# 06-uSD_Buttons_and_Buzzer.net
KiCad netlist of a schematic drawn in Altium Designer
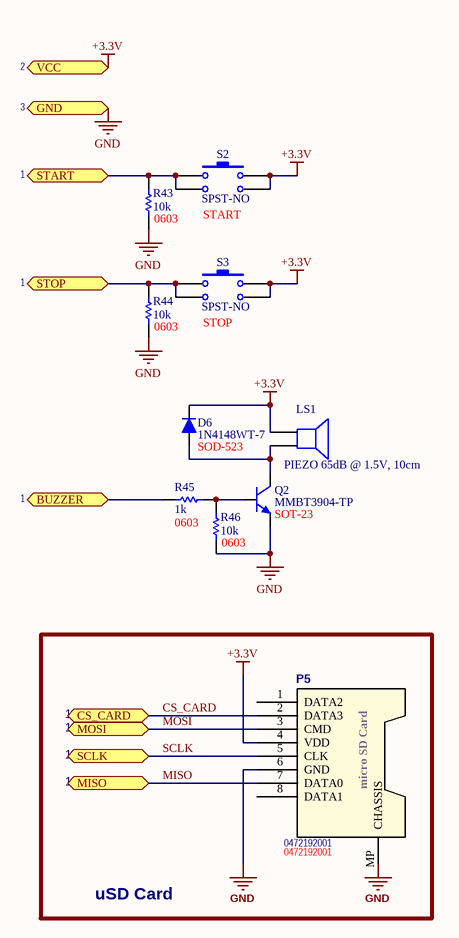
[diagram p0: 06-uSD, Buttons and Buzzer.SchDoc]

(export (version "E")
  (design (tool "Eeschema 10.0.6"))
  (components
    (comp (ref "D6")
      (value "1N4148WT-7")
      (footprint "SOD523")
      (description "Diode")
      (fields (field (name "PACKAGEREFERENCE") "SOD-523"))
      (libsource (lib "schematic_library") (part "DIODE"))
    )
    (comp (ref "LS1")
      (value "PIEZO 65dB @ 1.5V, 10cm")
      (footprint "PIEZO_XDCR_PKMCS0909E4000-R1")
      (description "Loudspeaker")
      (fields (field (name "MANUFACTURER PART NUMBER") "PKMCS0909E4000-R1"))
      (libsource (lib "Miscellaneous Devices") (part "Speaker"))
    )
    (comp (ref "P5")
      (value "0472192001")
      (footprint "MICROSD_MOLEX_0472192001")
      (description "Micro SD Card Slot 8-pin Push-In Push-Out")
      (fields (field (name "PACKAGEREFERENCE") "0472192001"))
      (libsource (lib "schematic_library") (part "microSD-114-00841-68"))
    )
    (comp (ref "Q2")
      (value "MMBT3904-TP")
      (footprint "SOT23-3")
      (description "TRANS NPN 40V 0.2A SOT-23")
      (fields (field (name "PACKAGEREFERENCE") "SOT-23"))
      (libsource (lib "schematic_library") (part "MMBT3904"))
    )
    (comp (ref "R43")
      (value "10k")
      (footprint "R0603")
      (description "Resistor")
      (fields
        (field (name "MANUFACTURER PART NUMBER") "RMCF0603FT10K0")
        (field (name "PACKAGEREFERENCE") "0603")
      )
      (libsource (lib "Miscellaneous Devices") (part "Res1"))
    )
    (comp (ref "R44")
      (value "10k")
      (footprint "R0603")
      (description "Resistor")
      (fields
        (field (name "MANUFACTURER PART NUMBER") "RMCF0603FT10K0")
        (field (name "PACKAGEREFERENCE") "0603")
      )
      (libsource (lib "Miscellaneous Devices") (part "Res1"))
    )
    (comp (ref "R45")
      (value "1k")
      (footprint "R0603")
      (description "Resistor")
      (fields
        (field (name "MANUFACTURER PART NUMBER") "RMCF0603FG1K00")
        (field (name "PACKAGEREFERENCE") "0603")
      )
      (libsource (lib "Miscellaneous Devices") (part "Res1"))
    )
    (comp (ref "R46")
      (value "10k")
      (footprint "R0603")
      (description "Resistor")
      (fields
        (field (name "MANUFACTURER PART NUMBER") "RMCF0603FT10K0")
        (field (name "PACKAGEREFERENCE") "0603")
      )
      (libsource (lib "Miscellaneous Devices") (part "Res1"))
    )
    (comp (ref "S2")
      (value "SPST-NO")
      (footprint "BUTTON_D6R90_GREEN")
      (description "Switch")
      (fields (field (name "MANUFACTURER PART NUMBER") "D6R50 F1 LFS") (field (name "FUNCTION") "START"))
      (libsource (lib "Library_Scott") (part "SW-PB"))
    )
    (comp (ref "S3")
      (value "SPST-NO")
      (footprint "BUTTON_D6R90_RED")
      (description "Switch")
      (fields (field (name "MANUFACTURER PART NUMBER") "D6R40 F1 LFS") (field (name "FUNCTION") "STOP"))
      (libsource (lib "Library_Scott") (part "SW-PB"))
    )
  )
  (nets
    (net (code "1") (name "+3.3V") (class "Default")
      (node (ref "D6") (pin "2") (pinfunction "K_2") (pintype "passive"))
      (node (ref "LS1") (pin "1") (pinfunction "1_1") (pintype "passive"))
      (node (ref "P5") (pin "4") (pinfunction "VDD_4") (pintype "passive"))
      (node (ref "S2") (pin "3") (pinfunction "3_3") (pintype "passive"))
      (node (ref "S2") (pin "4") (pinfunction "4_4") (pintype "passive"))
      (node (ref "S3") (pin "3") (pinfunction "3_3") (pintype "passive"))
      (node (ref "S3") (pin "4") (pinfunction "4_4") (pintype "passive"))
    )
    (net (code "2") (name "/BUZZER") (class "Default")
      (node (ref "R45") (pin "1") (pinfunction "1_1") (pintype "passive"))
    )
    (net (code "3") (name "/CS_CARD") (class "Default")
      (node (ref "P5") (pin "2") (pinfunction "DATA3_2") (pintype "passive"))
    )
    (net (code "4") (name "/MISO") (class "Default")
      (node (ref "P5") (pin "7") (pinfunction "DATA0_7") (pintype "passive"))
    )
    (net (code "5") (name "/MOSI") (class "Default")
      (node (ref "P5") (pin "3") (pinfunction "CMD_3") (pintype "passive"))
    )
    (net (code "6") (name "/SCLK") (class "Default")
      (node (ref "P5") (pin "5") (pinfunction "CLK_5") (pintype "passive"))
    )
    (net (code "7") (name "/START") (class "Default")
      (node (ref "R43") (pin "1") (pinfunction "1_1") (pintype "passive"))
      (node (ref "S2") (pin "1") (pinfunction "1_1") (pintype "passive"))
      (node (ref "S2") (pin "2") (pinfunction "2_2") (pintype "passive"))
    )
    (net (code "8") (name "/STOP") (class "Default")
      (node (ref "R44") (pin "1") (pinfunction "1_1") (pintype "passive"))
      (node (ref "S3") (pin "1") (pinfunction "1_1") (pintype "passive"))
      (node (ref "S3") (pin "2") (pinfunction "2_2") (pintype "passive"))
    )
    (net (code "9") (name "GND") (class "Default")
      (node (ref "P5") (pin "6") (pinfunction "GND_6") (pintype "passive"))
      (node (ref "P5") (pin "MP") (pinfunction "CHASSIS_MP") (pintype "passive"))
      (node (ref "Q2") (pin "1") (pinfunction "E_1") (pintype "passive"))
      (node (ref "R43") (pin "2") (pinfunction "2_2") (pintype "passive"))
      (node (ref "R44") (pin "2") (pinfunction "2_2") (pintype "passive"))
      (node (ref "R46") (pin "2") (pinfunction "2_2") (pintype "passive"))
    )
    (net (code "10") (name "Net-(D6-A)") (class "Default")
      (node (ref "D6") (pin "1") (pinfunction "A_1") (pintype "passive"))
      (node (ref "LS1") (pin "2") (pinfunction "2_2") (pintype "passive"))
      (node (ref "Q2") (pin "3") (pinfunction "C_3") (pintype "passive"))
    )
    (net (code "11") (name "Net-(Q2-B)") (class "Default")
      (node (ref "Q2") (pin "2") (pinfunction "B_2") (pintype "passive"))
      (node (ref "R45") (pin "2") (pinfunction "2_2") (pintype "passive"))
      (node (ref "R46") (pin "1") (pinfunction "1_1") (pintype "passive"))
    )
    (net (code "12") (name "unconnected-(P5-DATA1-Pad8)") (class "Default")
      (node (ref "P5") (pin "8") (pinfunction "DATA1_8") (pintype "passive"))
    )
    (net (code "13") (name "unconnected-(P5-DATA2-Pad1)") (class "Default")
      (node (ref "P5") (pin "1") (pinfunction "DATA2_1") (pintype "passive"))
    )
  )
)
